# CL02.net
KiCad netlist of a schematic drawn in EAGLE
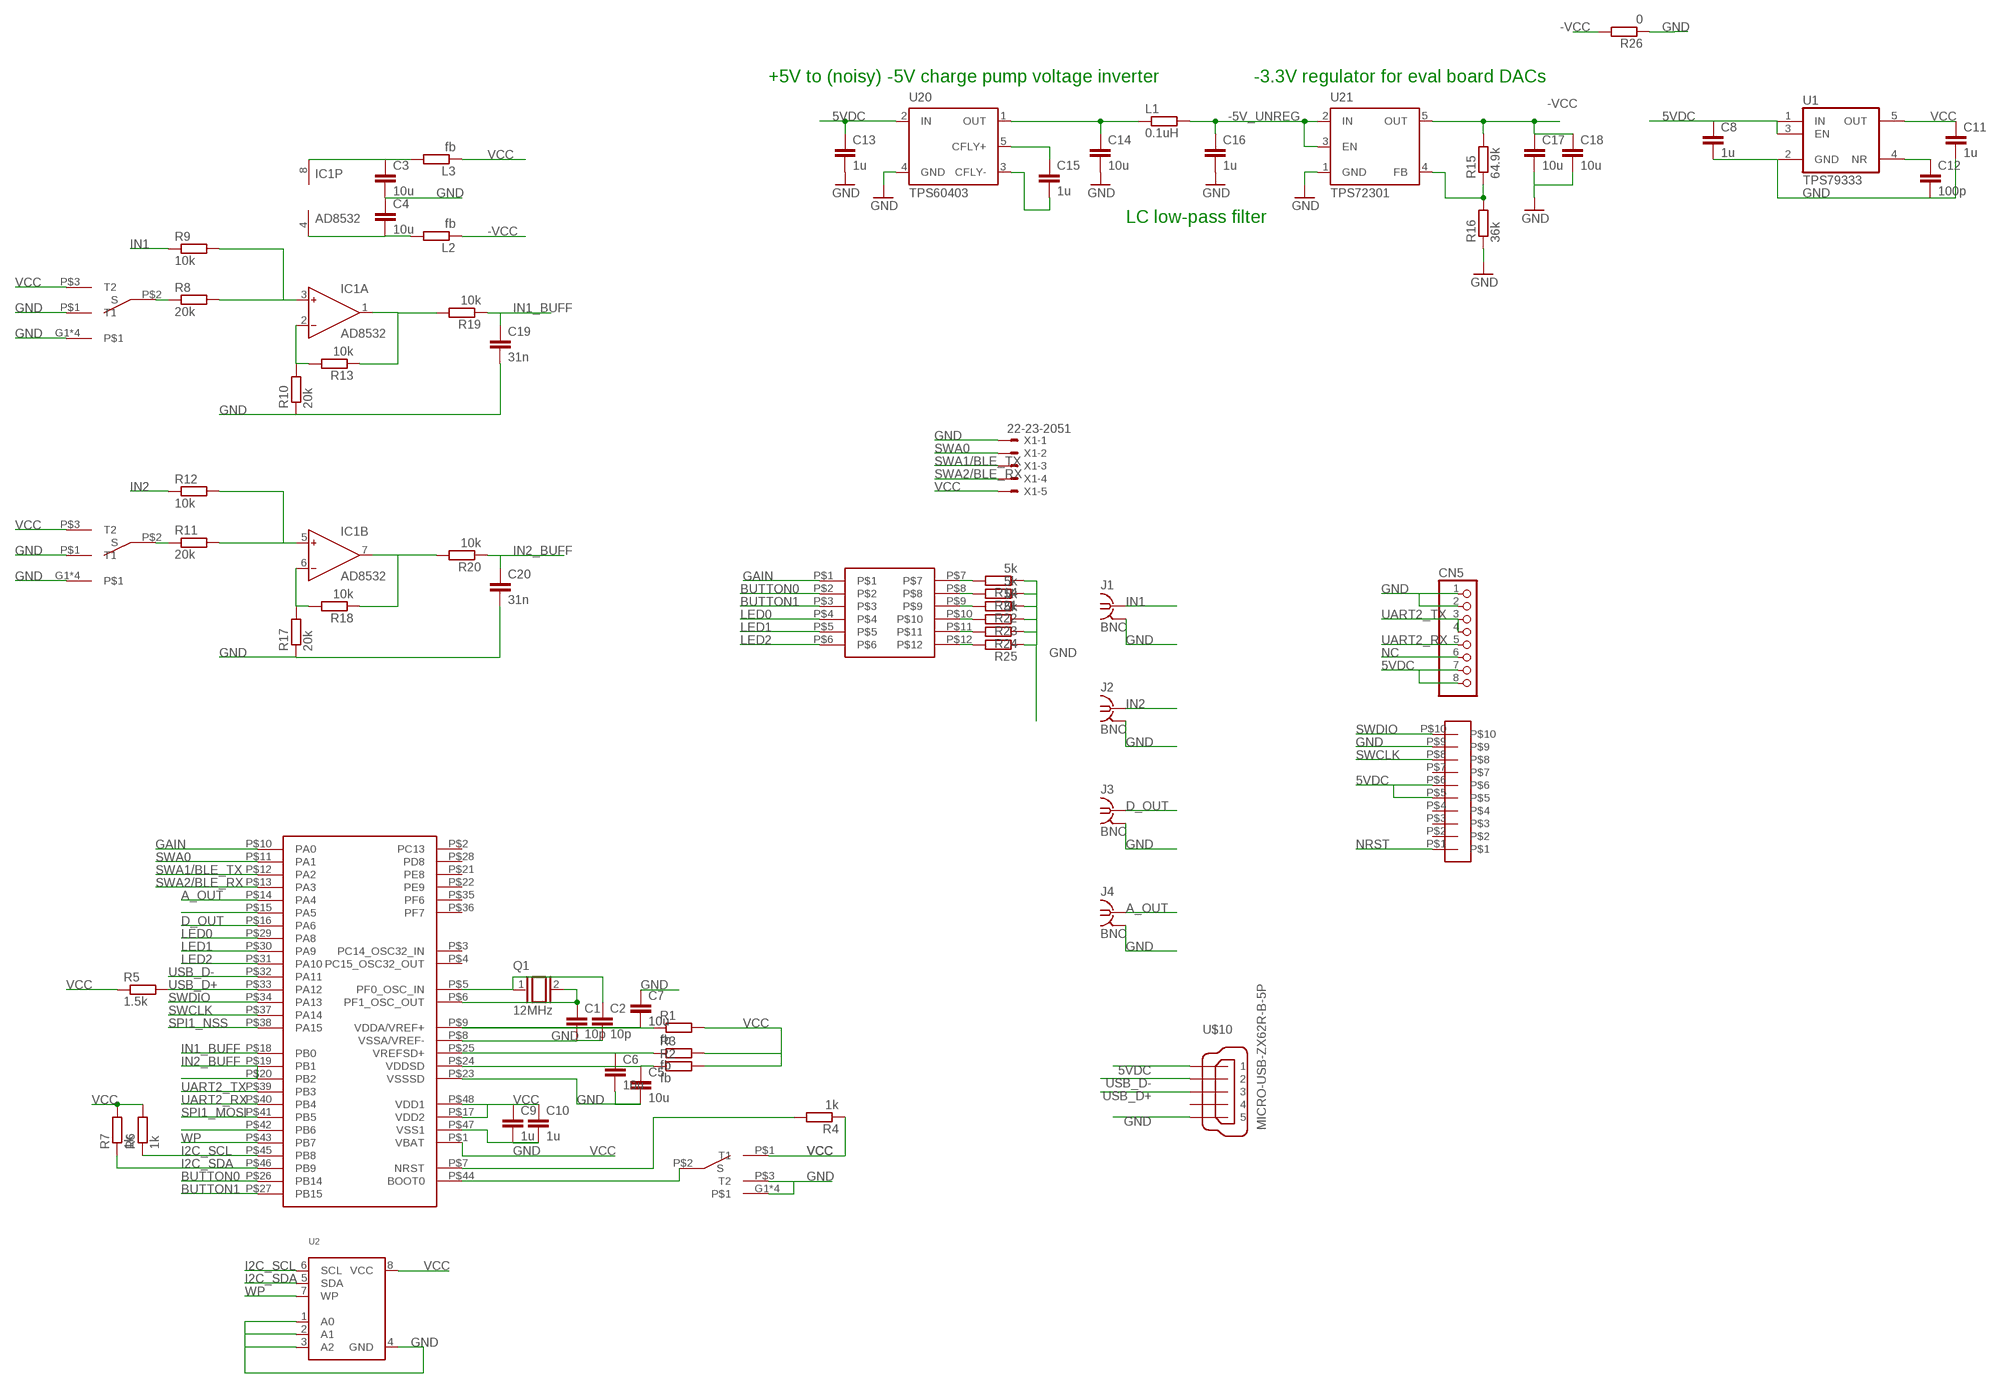
[diagram p0: schematic, sheet 1]

(export (version "E")
  (design (tool "Eeschema 10.0.6"))
  (components
    (comp (ref "C1")
      (value "10p")
      (footprint "eagle-import:C0402")
      (libsource (lib "eagle-import") (part "CC0402"))
    )
    (comp (ref "C2")
      (value "10p")
      (footprint "eagle-import:C0402")
      (libsource (lib "eagle-import") (part "CC0402"))
    )
    (comp (ref "C3")
      (value "10u")
      (footprint "eagle-import:C0402")
      (libsource (lib "eagle-import") (part "CC0402"))
    )
    (comp (ref "C4")
      (value "10u")
      (footprint "eagle-import:C0402")
      (libsource (lib "eagle-import") (part "CC0402"))
    )
    (comp (ref "C5")
      (value "10u")
      (footprint "eagle-import:C0402")
      (libsource (lib "eagle-import") (part "CC0402"))
    )
    (comp (ref "C6")
      (value "10u")
      (footprint "eagle-import:C0402")
      (libsource (lib "eagle-import") (part "CC0402"))
    )
    (comp (ref "C7")
      (value "10u")
      (footprint "eagle-import:C0402")
      (libsource (lib "eagle-import") (part "CC0402"))
    )
    (comp (ref "C8")
      (value "1u")
      (footprint "eagle-import:C0402")
      (libsource (lib "eagle-import") (part "CC0402"))
    )
    (comp (ref "C9")
      (value "1u")
      (footprint "eagle-import:C0402")
      (libsource (lib "eagle-import") (part "CC0402"))
    )
    (comp (ref "C10")
      (value "1u")
      (footprint "eagle-import:C0402")
      (libsource (lib "eagle-import") (part "CC0402"))
    )
    (comp (ref "C11")
      (value "1u")
      (footprint "eagle-import:C0402")
      (libsource (lib "eagle-import") (part "CC0402"))
    )
    (comp (ref "C12")
      (value "100p")
      (footprint "eagle-import:C0402")
      (libsource (lib "eagle-import") (part "CC0402"))
    )
    (comp (ref "C13")
      (value "1u")
      (footprint "eagle-import:C0402")
      (libsource (lib "eagle-import") (part "CC0402"))
    )
    (comp (ref "C14")
      (value "10u")
      (footprint "eagle-import:C0402")
      (libsource (lib "eagle-import") (part "CC0402"))
    )
    (comp (ref "C15")
      (value "1u")
      (footprint "eagle-import:C0402")
      (libsource (lib "eagle-import") (part "CC0402"))
    )
    (comp (ref "C16")
      (value "1u")
      (footprint "eagle-import:C0402")
      (libsource (lib "eagle-import") (part "CC0402"))
    )
    (comp (ref "C17")
      (value "10u")
      (footprint "eagle-import:C0402")
      (libsource (lib "eagle-import") (part "CC0402"))
    )
    (comp (ref "C18")
      (value "10u")
      (footprint "eagle-import:C0402")
      (libsource (lib "eagle-import") (part "CC0402"))
    )
    (comp (ref "C19")
      (value "31n")
      (footprint "eagle-import:C0402")
      (libsource (lib "eagle-import") (part "CC0402"))
    )
    (comp (ref "C20")
      (value "31n")
      (footprint "eagle-import:C0402")
      (libsource (lib "eagle-import") (part "CC0402"))
    )
    (comp (ref "CN5")
      (value "JST_8PIN")
      (footprint "eagle-import:JSTPH8")
      (libsource (lib "eagle-import") (part "JST_8PIN"))
    )
    (comp (ref "IC1")
      (value "AD8532")
      (footprint "eagle-import:SO8")
      (fields (field (name "MF") "ALTERA CORPORATION") (field (name "MPN") "AD8542ARZ-REEL"))
      (libsource (lib "eagle-import") (part "AD8542R"))
    )
    (comp (ref "J1")
      (value "BNC")
      (footprint "eagle-import:BNC-SOCKET")
      (libsource (lib "eagle-import") (part "BNC"))
    )
    (comp (ref "J2")
      (value "BNC")
      (footprint "eagle-import:BNC-SOCKET")
      (libsource (lib "eagle-import") (part "BNC"))
    )
    (comp (ref "J3")
      (value "BNC")
      (footprint "eagle-import:BNC-SOCKET")
      (libsource (lib "eagle-import") (part "BNC"))
    )
    (comp (ref "J4")
      (value "BNC")
      (footprint "eagle-import:BNC-SOCKET")
      (libsource (lib "eagle-import") (part "BNC"))
    )
    (comp (ref "L1")
      (value "0.1uH")
      (footprint "eagle-import:R0402")
      (libsource (lib "eagle-import") (part "RR0402"))
    )
    (comp (ref "L2")
      (value "fb")
      (footprint "eagle-import:R0402")
      (libsource (lib "eagle-import") (part "RR0402"))
    )
    (comp (ref "L3")
      (value "fb")
      (footprint "eagle-import:R0402")
      (libsource (lib "eagle-import") (part "RR0402"))
    )
    (comp (ref "Q1")
      (value "12MHz")
      (footprint "eagle-import:QS")
      (libsource (lib "eagle-import") (part "XTAL/S"))
    )
    (comp (ref "R1")
      (value "fb")
      (footprint "eagle-import:R0402")
      (libsource (lib "eagle-import") (part "RR0402"))
    )
    (comp (ref "R2")
      (value "fb")
      (footprint "eagle-import:R0402")
      (libsource (lib "eagle-import") (part "RR0402"))
    )
    (comp (ref "R3")
      (value "fb")
      (footprint "eagle-import:R0402")
      (libsource (lib "eagle-import") (part "RR0402"))
    )
    (comp (ref "R4")
      (value "1k")
      (footprint "eagle-import:R0402")
      (libsource (lib "eagle-import") (part "RR0402"))
    )
    (comp (ref "R5")
      (value "1.5k")
      (footprint "eagle-import:R0402")
      (libsource (lib "eagle-import") (part "RR0402"))
    )
    (comp (ref "R6")
      (value "1k")
      (footprint "eagle-import:R0402")
      (libsource (lib "eagle-import") (part "RR0402"))
    )
    (comp (ref "R7")
      (value "1k")
      (footprint "eagle-import:R0402")
      (libsource (lib "eagle-import") (part "RR0402"))
    )
    (comp (ref "R8")
      (value "20k")
      (footprint "eagle-import:R0402")
      (libsource (lib "eagle-import") (part "RR0402"))
    )
    (comp (ref "R9")
      (value "10k")
      (footprint "eagle-import:R0402")
      (libsource (lib "eagle-import") (part "RR0402"))
    )
    (comp (ref "R10")
      (value "20k")
      (footprint "eagle-import:R0402")
      (libsource (lib "eagle-import") (part "RR0402"))
    )
    (comp (ref "R11")
      (value "20k")
      (footprint "eagle-import:R0402")
      (libsource (lib "eagle-import") (part "RR0402"))
    )
    (comp (ref "R12")
      (value "10k")
      (footprint "eagle-import:R0402")
      (libsource (lib "eagle-import") (part "RR0402"))
    )
    (comp (ref "R13")
      (value "10k")
      (footprint "eagle-import:R0402")
      (libsource (lib "eagle-import") (part "RR0402"))
    )
    (comp (ref "R14")
      (value "5k")
      (footprint "eagle-import:R0402")
      (libsource (lib "eagle-import") (part "RR0402"))
    )
    (comp (ref "R15")
      (value "64.9k")
      (footprint "eagle-import:R0402")
      (libsource (lib "eagle-import") (part "RR0402"))
    )
    (comp (ref "R16")
      (value "36k")
      (footprint "eagle-import:R0402")
      (libsource (lib "eagle-import") (part "RR0402"))
    )
    (comp (ref "R17")
      (value "20k")
      (footprint "eagle-import:R0402")
      (libsource (lib "eagle-import") (part "RR0402"))
    )
    (comp (ref "R18")
      (value "10k")
      (footprint "eagle-import:R0402")
      (libsource (lib "eagle-import") (part "RR0402"))
    )
    (comp (ref "R19")
      (value "10k")
      (footprint "eagle-import:R0402")
      (libsource (lib "eagle-import") (part "RR0402"))
    )
    (comp (ref "R20")
      (value "10k")
      (footprint "eagle-import:R0402")
      (libsource (lib "eagle-import") (part "RR0402"))
    )
    (comp (ref "R21")
      (value "5k")
      (footprint "eagle-import:R0402")
      (libsource (lib "eagle-import") (part "RR0402"))
    )
    (comp (ref "R22")
      (value "5k")
      (footprint "eagle-import:R0402")
      (libsource (lib "eagle-import") (part "RR0402"))
    )
    (comp (ref "R23")
      (value "5k")
      (footprint "eagle-import:R0402")
      (libsource (lib "eagle-import") (part "RR0402"))
    )
    (comp (ref "R24")
      (value "RR0402")
      (footprint "eagle-import:R0402")
      (libsource (lib "eagle-import") (part "RR0402"))
    )
    (comp (ref "R25")
      (value "RR0402")
      (footprint "eagle-import:R0402")
      (libsource (lib "eagle-import") (part "RR0402"))
    )
    (comp (ref "R26")
      (value "0")
      (footprint "eagle-import:R0402")
      (libsource (lib "eagle-import") (part "RR0402"))
    )
    (comp (ref "U$1")
      (value "STM32F373CCT6")
      (footprint "eagle-import:LQFP48")
      (libsource (lib "eagle-import") (part "STM32F373CCT6"))
    )
    (comp (ref "U$6")
      (value "CUS-12B")
      (footprint "eagle-import:CUS-12B")
      (libsource (lib "eagle-import") (part "CUS-12B"))
    )
    (comp (ref "U$7")
      (value "CUS-12B")
      (footprint "eagle-import:CUS-12B")
      (libsource (lib "eagle-import") (part "CUS-12B"))
    )
    (comp (ref "U$8")
      (value "2.54MM_2X6")
      (footprint "eagle-import:2.54MM_2X6")
      (libsource (lib "eagle-import") (part "2.54MM_2X6"))
    )
    (comp (ref "U$9")
      (value "2.54MM_2X5")
      (footprint "eagle-import:2.54MM_2X5")
      (libsource (lib "eagle-import") (part "2.54MM_2X5"))
    )
    (comp (ref "U$10")
      (value "MICRO-USB-ZX62R-B-5P")
      (footprint "eagle-import:ZX62R-B-5P")
      (libsource (lib "eagle-import") (part "MICRO-USB-ZX62R-B-5P"))
    )
    (comp (ref "U$12")
      (value "CUS-12B")
      (footprint "eagle-import:CUS-12B")
      (libsource (lib "eagle-import") (part "CUS-12B"))
    )
    (comp (ref "U1")
      (value "TPS79333")
      (footprint "eagle-import:TSOT-23-5")
      (libsource (lib "eagle-import") (part "TPS79333"))
    )
    (comp (ref "U2")
      (value "EEPROM_I2C_SOIC8_GENERIC")
      (footprint "eagle-import:SOIC8_150MIL")
      (libsource (lib "eagle-import") (part "EEPROM_I2C_SOIC8_GENERIC"))
    )
    (comp (ref "U20")
      (value "TPS60403")
      (footprint "eagle-import:SOT-23-5")
      (libsource (lib "eagle-import") (part "TPS60403"))
    )
    (comp (ref "U21")
      (value "TPS72301")
      (footprint "eagle-import:SOT-23-5")
      (libsource (lib "eagle-import") (part "TPS72301"))
    )
    (comp (ref "X1")
      (value "22-23-2051")
      (footprint "eagle-import:22-23-2051")
      (fields (field (name "MF") "MOLEX"))
      (libsource (lib "eagle-import") (part "22-23-2051"))
    )
  )
  (nets
    (net (code "1") (name "/-5V_UNREG") (class "Default")
      (node (ref "C16") (pin "1") (pinfunction "1_1") (pintype "passive"))
      (node (ref "L1") (pin "2") (pinfunction "2_2") (pintype "passive"))
      (node (ref "U21") (pin "2") (pinfunction "IN_2") (pintype "power_in"))
      (node (ref "U21") (pin "3") (pinfunction "EN_3") (pintype "input"))
    )
    (net (code "2") (name "/-VCC") (class "Default")
      (node (ref "C17") (pin "1") (pinfunction "1_1") (pintype "passive"))
      (node (ref "C18") (pin "1") (pinfunction "1_1") (pintype "passive"))
      (node (ref "L2") (pin "1") (pinfunction "1_1") (pintype "passive"))
      (node (ref "R15") (pin "2") (pinfunction "2_2") (pintype "passive"))
      (node (ref "R26") (pin "2") (pinfunction "2_2") (pintype "passive"))
      (node (ref "U21") (pin "5") (pinfunction "OUT_5") (pintype "power_in"))
    )
    (net (code "3") (name "/5VDC") (class "Default")
      (node (ref "C13") (pin "1") (pinfunction "1_1") (pintype "passive"))
      (node (ref "C8") (pin "1") (pinfunction "1_1") (pintype "passive"))
      (node (ref "CN5") (pin "7") (pinfunction "7_7") (pintype "passive"))
      (node (ref "CN5") (pin "8") (pinfunction "8_8") (pintype "passive"))
      (node (ref "U$10") (pin "1") (pinfunction "1_1") (pintype "input"))
      (node (ref "U$9") (pin "P$5") (pinfunction "P$5_P$5") (pintype "bidirectional"))
      (node (ref "U$9") (pin "P$6") (pinfunction "P$6_P$6") (pintype "bidirectional"))
      (node (ref "U1") (pin "1") (pinfunction "IN_1") (pintype "power_in"))
      (node (ref "U1") (pin "3") (pinfunction "EN_3") (pintype "input"))
      (node (ref "U20") (pin "2") (pinfunction "IN_2") (pintype "power_in"))
    )
    (net (code "4") (name "/A_OUT") (class "Default")
      (node (ref "J4") (pin "A") (pinfunction "1_A") (pintype "passive"))
      (node (ref "U$1") (pin "P$14") (pinfunction "PA4_P$14") (pintype "bidirectional"))
    )
    (net (code "5") (name "/BUTTON0") (class "Default")
      (node (ref "U$1") (pin "P$26") (pinfunction "PB14_P$26") (pintype "bidirectional"))
      (node (ref "U$8") (pin "P$2") (pinfunction "P$2_P$2") (pintype "bidirectional"))
    )
    (net (code "6") (name "/BUTTON1") (class "Default")
      (node (ref "U$1") (pin "P$27") (pinfunction "PB15_P$27") (pintype "bidirectional"))
      (node (ref "U$8") (pin "P$3") (pinfunction "P$3_P$3") (pintype "bidirectional"))
    )
    (net (code "7") (name "/D_OUT") (class "Default")
      (node (ref "J3") (pin "A") (pinfunction "1_A") (pintype "passive"))
      (node (ref "U$1") (pin "P$16") (pinfunction "PA6_P$16") (pintype "bidirectional"))
    )
    (net (code "8") (name "/GAIN") (class "Default")
      (node (ref "U$1") (pin "P$10") (pinfunction "PA0_P$10") (pintype "bidirectional"))
      (node (ref "U$8") (pin "P$1") (pinfunction "P$1_P$1") (pintype "bidirectional"))
    )
    (net (code "9") (name "/I2C_SCL") (class "Default")
      (node (ref "R6") (pin "1") (pinfunction "1_1") (pintype "passive"))
      (node (ref "U$1") (pin "P$45") (pinfunction "PB8_P$45") (pintype "bidirectional"))
      (node (ref "U2") (pin "6") (pinfunction "SCL_6") (pintype "input"))
    )
    (net (code "10") (name "/I2C_SDA") (class "Default")
      (node (ref "R7") (pin "1") (pinfunction "1_1") (pintype "passive"))
      (node (ref "U$1") (pin "P$46") (pinfunction "PB9_P$46") (pintype "bidirectional"))
      (node (ref "U2") (pin "5") (pinfunction "SDA_5") (pintype "bidirectional"))
    )
    (net (code "11") (name "/IN1") (class "Default")
      (node (ref "J1") (pin "A") (pinfunction "1_A") (pintype "passive"))
      (node (ref "R9") (pin "1") (pinfunction "1_1") (pintype "passive"))
    )
    (net (code "12") (name "/IN1_BUFF") (class "Default")
      (node (ref "C19") (pin "1") (pinfunction "1_1") (pintype "passive"))
      (node (ref "R19") (pin "1") (pinfunction "1_1") (pintype "passive"))
      (node (ref "U$1") (pin "P$18") (pinfunction "PB0_P$18") (pintype "bidirectional"))
    )
    (net (code "13") (name "/IN2") (class "Default")
      (node (ref "J2") (pin "A") (pinfunction "1_A") (pintype "passive"))
      (node (ref "R12") (pin "1") (pinfunction "1_1") (pintype "passive"))
    )
    (net (code "14") (name "/IN2_BUFF") (class "Default")
      (node (ref "C20") (pin "1") (pinfunction "1_1") (pintype "passive"))
      (node (ref "R20") (pin "1") (pinfunction "1_1") (pintype "passive"))
      (node (ref "U$1") (pin "P$19") (pinfunction "PB1_P$19") (pintype "bidirectional"))
      (node (ref "U$1") (pin "P$20") (pinfunction "PB2_P$20") (pintype "bidirectional"))
    )
    (net (code "15") (name "/LED0") (class "Default")
      (node (ref "U$1") (pin "P$29") (pinfunction "PA8_P$29") (pintype "bidirectional"))
      (node (ref "U$8") (pin "P$4") (pinfunction "P$4_P$4") (pintype "bidirectional"))
    )
    (net (code "16") (name "/LED1") (class "Default")
      (node (ref "U$1") (pin "P$30") (pinfunction "PA9_P$30") (pintype "bidirectional"))
      (node (ref "U$8") (pin "P$5") (pinfunction "P$5_P$5") (pintype "bidirectional"))
    )
    (net (code "17") (name "/LED2") (class "Default")
      (node (ref "U$1") (pin "P$31") (pinfunction "PA10_P$31") (pintype "bidirectional"))
      (node (ref "U$8") (pin "P$6") (pinfunction "P$6_P$6") (pintype "bidirectional"))
    )
    (net (code "18") (name "/NC") (class "Default")
      (node (ref "CN5") (pin "6") (pinfunction "6_6") (pintype "passive"))
    )
    (net (code "19") (name "/NRST") (class "Default")
      (node (ref "R4") (pin "2") (pinfunction "2_2") (pintype "passive"))
      (node (ref "U$1") (pin "P$7") (pinfunction "NRST_P$7") (pintype "bidirectional"))
      (node (ref "U$9") (pin "P$1") (pinfunction "P$1_P$1") (pintype "bidirectional"))
    )
    (net (code "20") (name "/SPI1_MOSI") (class "Default")
      (node (ref "U$1") (pin "P$41") (pinfunction "PB5_P$41") (pintype "bidirectional"))
    )
    (net (code "21") (name "/SPI1_NSS") (class "Default")
      (node (ref "U$1") (pin "P$38") (pinfunction "PA15_P$38") (pintype "bidirectional"))
    )
    (net (code "22") (name "/SWA0") (class "Default")
      (node (ref "U$1") (pin "P$11") (pinfunction "PA1_P$11") (pintype "bidirectional"))
      (node (ref "X1") (pin "2") (pinfunction "S_2") (pintype "passive"))
    )
    (net (code "23") (name "/SWA1{slash}BLE_TX") (class "Default")
      (node (ref "U$1") (pin "P$12") (pinfunction "PA2_P$12") (pintype "bidirectional"))
      (node (ref "X1") (pin "3") (pinfunction "S_3") (pintype "passive"))
    )
    (net (code "24") (name "/SWA2{slash}BLE_RX") (class "Default")
      (node (ref "U$1") (pin "P$13") (pinfunction "PA3_P$13") (pintype "bidirectional"))
      (node (ref "X1") (pin "4") (pinfunction "S_4") (pintype "passive"))
    )
    (net (code "25") (name "/SWCLK") (class "Default")
      (node (ref "U$1") (pin "P$37") (pinfunction "PA14_P$37") (pintype "bidirectional"))
      (node (ref "U$9") (pin "P$8") (pinfunction "P$8_P$8") (pintype "bidirectional"))
    )
    (net (code "26") (name "/SWDIO") (class "Default")
      (node (ref "U$1") (pin "P$34") (pinfunction "PA13_P$34") (pintype "bidirectional"))
      (node (ref "U$9") (pin "P$10") (pinfunction "P$10_P$10") (pintype "bidirectional"))
    )
    (net (code "27") (name "/UART2_RX") (class "Default")
      (node (ref "CN5") (pin "5") (pinfunction "5_5") (pintype "passive"))
      (node (ref "U$1") (pin "P$40") (pinfunction "PB4_P$40") (pintype "bidirectional"))
    )
    (net (code "28") (name "/UART2_TX") (class "Default")
      (node (ref "CN5") (pin "3") (pinfunction "3_3") (pintype "passive"))
      (node (ref "CN5") (pin "4") (pinfunction "4_4") (pintype "passive"))
      (node (ref "U$1") (pin "P$39") (pinfunction "PB3_P$39") (pintype "bidirectional"))
    )
    (net (code "29") (name "/USB_D+") (class "Default")
      (node (ref "R5") (pin "2") (pinfunction "2_2") (pintype "passive"))
      (node (ref "U$1") (pin "P$33") (pinfunction "PA12_P$33") (pintype "bidirectional"))
      (node (ref "U$10") (pin "3") (pinfunction "3_3") (pintype "input"))
    )
    (net (code "30") (name "/USB_D-") (class "Default")
      (node (ref "U$1") (pin "P$32") (pinfunction "PA11_P$32") (pintype "bidirectional"))
      (node (ref "U$10") (pin "2") (pinfunction "2_2") (pintype "input"))
    )
    (net (code "31") (name "/VCC") (class "Default")
      (node (ref "C10") (pin "1") (pinfunction "1_1") (pintype "passive"))
      (node (ref "C11") (pin "1") (pinfunction "1_1") (pintype "passive"))
      (node (ref "C9") (pin "1") (pinfunction "1_1") (pintype "passive"))
      (node (ref "L3") (pin "1") (pinfunction "1_1") (pintype "passive"))
      (node (ref "R1") (pin "2") (pinfunction "2_2") (pintype "passive"))
      (node (ref "R2") (pin "2") (pinfunction "2_2") (pintype "passive"))
      (node (ref "R3") (pin "2") (pinfunction "2_2") (pintype "passive"))
      (node (ref "R4") (pin "1") (pinfunction "1_1") (pintype "passive"))
      (node (ref "R5") (pin "1") (pinfunction "1_1") (pintype "passive"))
      (node (ref "R6") (pin "2") (pinfunction "2_2") (pintype "passive"))
      (node (ref "R7") (pin "2") (pinfunction "2_2") (pintype "passive"))
      (node (ref "U$1") (pin "P$1") (pinfunction "VBAT_P$1") (pintype "bidirectional"))
      (node (ref "U$1") (pin "P$17") (pinfunction "VDD2_P$17") (pintype "bidirectional"))
      (node (ref "U$1") (pin "P$48") (pinfunction "VDD1_P$48") (pintype "bidirectional"))
      (node (ref "U$12") (pin "P$1") (pinfunction "T1_P$1") (pintype "bidirectional"))
      (node (ref "U$6") (pin "P$3") (pinfunction "T2_P$3") (pintype "bidirectional"))
      (node (ref "U$7") (pin "P$3") (pinfunction "T2_P$3") (pintype "bidirectional"))
      (node (ref "U1") (pin "5") (pinfunction "OUT_5") (pintype "power_in"))
      (node (ref "U2") (pin "8") (pinfunction "VCC_8") (pintype "power_in"))
      (node (ref "X1") (pin "5") (pinfunction "S_5") (pintype "passive"))
    )
    (net (code "32") (name "/WP") (class "Default")
      (node (ref "U$1") (pin "P$43") (pinfunction "PB7_P$43") (pintype "bidirectional"))
      (node (ref "U2") (pin "7") (pinfunction "WP_7") (pintype "input"))
    )
    (net (code "33") (name "GND") (class "Default")
      (node (ref "C1") (pin "2") (pinfunction "2_2") (pintype "passive"))
      (node (ref "C10") (pin "2") (pinfunction "2_2") (pintype "passive"))
      (node (ref "C11") (pin "2") (pinfunction "2_2") (pintype "passive"))
      (node (ref "C12") (pin "2") (pinfunction "2_2") (pintype "passive"))
      (node (ref "C13") (pin "2") (pinfunction "2_2") (pintype "passive"))
      (node (ref "C14") (pin "2") (pinfunction "2_2") (pintype "passive"))
      (node (ref "C16") (pin "2") (pinfunction "2_2") (pintype "passive"))
      (node (ref "C17") (pin "2") (pinfunction "2_2") (pintype "passive"))
      (node (ref "C18") (pin "2") (pinfunction "2_2") (pintype "passive"))
      (node (ref "C19") (pin "2") (pinfunction "2_2") (pintype "passive"))
      (node (ref "C2") (pin "2") (pinfunction "2_2") (pintype "passive"))
      (node (ref "C20") (pin "2") (pinfunction "2_2") (pintype "passive"))
      (node (ref "C3") (pin "2") (pinfunction "2_2") (pintype "passive"))
      (node (ref "C4") (pin "1") (pinfunction "1_1") (pintype "passive"))
      (node (ref "C5") (pin "2") (pinfunction "2_2") (pintype "passive"))
      (node (ref "C6") (pin "2") (pinfunction "2_2") (pintype "passive"))
      (node (ref "C7") (pin "1") (pinfunction "1_1") (pintype "passive"))
      (node (ref "C8") (pin "2") (pinfunction "2_2") (pintype "passive"))
      (node (ref "C9") (pin "2") (pinfunction "2_2") (pintype "passive"))
      (node (ref "CN5") (pin "1") (pinfunction "1_1") (pintype "passive"))
      (node (ref "CN5") (pin "2") (pinfunction "2_2") (pintype "passive"))
      (node (ref "J1") (pin "SH") (pinfunction "SH_SH") (pintype "power_in"))
      (node (ref "J2") (pin "SH") (pinfunction "SH_SH") (pintype "power_in"))
      (node (ref "J3") (pin "SH") (pinfunction "SH_SH") (pintype "power_in"))
      (node (ref "J4") (pin "SH") (pinfunction "SH_SH") (pintype "power_in"))
      (node (ref "R10") (pin "1") (pinfunction "1_1") (pintype "passive"))
      (node (ref "R14") (pin "1") (pinfunction "1_1") (pintype "passive"))
      (node (ref "R16") (pin "1") (pinfunction "1_1") (pintype "passive"))
      (node (ref "R17") (pin "1") (pinfunction "1_1") (pintype "passive"))
      (node (ref "R21") (pin "1") (pinfunction "1_1") (pintype "passive"))
      (node (ref "R22") (pin "1") (pinfunction "1_1") (pintype "passive"))
      (node (ref "R23") (pin "1") (pinfunction "1_1") (pintype "passive"))
      (node (ref "R24") (pin "1") (pinfunction "1_1") (pintype "passive"))
      (node (ref "R25") (pin "1") (pinfunction "1_1") (pintype "passive"))
      (node (ref "R26") (pin "1") (pinfunction "1_1") (pintype "passive"))
      (node (ref "U$1") (pin "P$23") (pinfunction "VSSSD_P$23") (pintype "bidirectional"))
      (node (ref "U$1") (pin "P$47") (pinfunction "VSS1_P$47") (pintype "bidirectional"))
      (node (ref "U$1") (pin "P$8") (pinfunction "VSSA/VREF-_P$8") (pintype "bidirectional"))
      (node (ref "U$10") (pin "5") (pinfunction "5_5") (pintype "input"))
      (node (ref "U$12") (pin "G1") (pinfunction "P$1_G1") (pintype "bidirectional"))
      (node (ref "U$12") (pin "G2") (pinfunction "P$1_G2") (pintype "bidirectional"))
      (node (ref "U$12") (pin "G3") (pinfunction "P$1_G3") (pintype "bidirectional"))
      (node (ref "U$12") (pin "G4") (pinfunction "P$1_G4") (pintype "bidirectional"))
      (node (ref "U$12") (pin "P$3") (pinfunction "T2_P$3") (pintype "bidirectional"))
      (node (ref "U$6") (pin "G1") (pinfunction "P$1_G1") (pintype "bidirectional"))
      (node (ref "U$6") (pin "G2") (pinfunction "P$1_G2") (pintype "bidirectional"))
      (node (ref "U$6") (pin "G3") (pinfunction "P$1_G3") (pintype "bidirectional"))
      (node (ref "U$6") (pin "G4") (pinfunction "P$1_G4") (pintype "bidirectional"))
      (node (ref "U$6") (pin "P$1") (pinfunction "T1_P$1") (pintype "bidirectional"))
      (node (ref "U$7") (pin "G1") (pinfunction "P$1_G1") (pintype "bidirectional"))
      (node (ref "U$7") (pin "G2") (pinfunction "P$1_G2") (pintype "bidirectional"))
      (node (ref "U$7") (pin "G3") (pinfunction "P$1_G3") (pintype "bidirectional"))
      (node (ref "U$7") (pin "G4") (pinfunction "P$1_G4") (pintype "bidirectional"))
      (node (ref "U$7") (pin "P$1") (pinfunction "T1_P$1") (pintype "bidirectional"))
      (node (ref "U$9") (pin "P$9") (pinfunction "P$9_P$9") (pintype "bidirectional"))
      (node (ref "U1") (pin "2") (pinfunction "GND_2") (pintype "power_in"))
      (node (ref "U2") (pin "1") (pinfunction "A0_1") (pintype "input"))
      (node (ref "U2") (pin "2") (pinfunction "A1_2") (pintype "input"))
      (node (ref "U2") (pin "3") (pinfunction "A2_3") (pintype "input"))
      (node (ref "U2") (pin "4") (pinfunction "GND_4") (pintype "power_in"))
      (node (ref "U20") (pin "4") (pinfunction "GND_4") (pintype "power_in"))
      (node (ref "U21") (pin "1") (pinfunction "GND_1") (pintype "power_in"))
      (node (ref "X1") (pin "1") (pinfunction "S_1") (pintype "passive"))
    )
    (net (code "34") (name "Net-(IC1A-IN+)") (class "Default")
      (node (ref "IC1") (pin "3") (pinfunction "IN+_3") (pintype "input"))
      (node (ref "R8") (pin "2") (pinfunction "2_2") (pintype "passive"))
      (node (ref "R9") (pin "2") (pinfunction "2_2") (pintype "passive"))
    )
    (net (code "35") (name "Net-(IC1A-IN-)") (class "Default")
      (node (ref "IC1") (pin "2") (pinfunction "IN-_2") (pintype "input"))
      (node (ref "R10") (pin "2") (pinfunction "2_2") (pintype "passive"))
      (node (ref "R13") (pin "2") (pinfunction "2_2") (pintype "passive"))
    )
    (net (code "36") (name "Net-(IC1A-OUT)") (class "Default")
      (node (ref "IC1") (pin "1") (pinfunction "OUT_1") (pintype "output"))
      (node (ref "R13") (pin "1") (pinfunction "1_1") (pintype "passive"))
      (node (ref "R19") (pin "2") (pinfunction "2_2") (pintype "passive"))
    )
    (net (code "37") (name "Net-(IC1B-IN+)") (class "Default")
      (node (ref "IC1") (pin "5") (pinfunction "IN+_5") (pintype "input"))
      (node (ref "R11") (pin "2") (pinfunction "2_2") (pintype "passive"))
      (node (ref "R12") (pin "2") (pinfunction "2_2") (pintype "passive"))
    )
    (net (code "38") (name "Net-(IC1B-IN-)") (class "Default")
      (node (ref "IC1") (pin "6") (pinfunction "IN-_6") (pintype "input"))
      (node (ref "R17") (pin "2") (pinfunction "2_2") (pintype "passive"))
      (node (ref "R18") (pin "2") (pinfunction "2_2") (pintype "passive"))
    )
    (net (code "39") (name "Net-(IC1B-OUT)") (class "Default")
      (node (ref "IC1") (pin "7") (pinfunction "OUT_7") (pintype "output"))
      (node (ref "R18") (pin "1") (pinfunction "1_1") (pintype "passive"))
      (node (ref "R20") (pin "2") (pinfunction "2_2") (pintype "passive"))
    )
    (net (code "40") (name "Net-(IC1C-V+)") (class "Default")
      (node (ref "C3") (pin "1") (pinfunction "1_1") (pintype "passive"))
      (node (ref "IC1") (pin "8") (pinfunction "V+_8") (pintype "power_in"))
      (node (ref "L3") (pin "2") (pinfunction "2_2") (pintype "passive"))
    )
    (net (code "41") (name "Net-(IC1C-V-)") (class "Default")
      (node (ref "C4") (pin "2") (pinfunction "2_2") (pintype "passive"))
      (node (ref "IC1") (pin "4") (pinfunction "V-_4") (pintype "power_in"))
      (node (ref "L2") (pin "2") (pinfunction "2_2") (pintype "passive"))
    )
    (net (code "42") (name "Net-(R14-Pad2)") (class "Default")
      (node (ref "R14") (pin "2") (pinfunction "2_2") (pintype "passive"))
      (node (ref "U$8") (pin "P$7") (pinfunction "P$7_P$7") (pintype "bidirectional"))
    )
    (net (code "43") (name "Net-(R21-Pad2)") (class "Default")
      (node (ref "R21") (pin "2") (pinfunction "2_2") (pintype "passive"))
      (node (ref "U$8") (pin "P$8") (pinfunction "P$8_P$8") (pintype "bidirectional"))
    )
    (net (code "44") (name "Net-(R22-Pad2)") (class "Default")
      (node (ref "R22") (pin "2") (pinfunction "2_2") (pintype "passive"))
      (node (ref "U$8") (pin "P$9") (pinfunction "P$9_P$9") (pintype "bidirectional"))
    )
    (net (code "45") (name "Net-(R23-Pad2)") (class "Default")
      (node (ref "R23") (pin "2") (pinfunction "2_2") (pintype "passive"))
      (node (ref "U$8") (pin "P$10") (pinfunction "P$10_P$10") (pintype "bidirectional"))
    )
    (net (code "46") (name "Net-(R24-Pad2)") (class "Default")
      (node (ref "R24") (pin "2") (pinfunction "2_2") (pintype "passive"))
      (node (ref "U$8") (pin "P$11") (pinfunction "P$11_P$11") (pintype "bidirectional"))
    )
    (net (code "47") (name "Net-(R25-Pad2)") (class "Default")
      (node (ref "R25") (pin "2") (pinfunction "2_2") (pintype "passive"))
      (node (ref "U$8") (pin "P$12") (pinfunction "P$12_P$12") (pintype "bidirectional"))
    )
    (net (code "48") (name "Net-(U$1-BOOT0)") (class "Default")
      (node (ref "U$1") (pin "P$44") (pinfunction "BOOT0_P$44") (pintype "bidirectional"))
      (node (ref "U$12") (pin "P$2") (pinfunction "S_P$2") (pintype "bidirectional"))
    )
    (net (code "49") (name "Net-(U$1-PF0_OSC_IN)") (class "Default")
      (node (ref "C2") (pin "1") (pinfunction "1_1") (pintype "passive"))
      (node (ref "Q1") (pin "1") (pinfunction "1_1") (pintype "passive"))
      (node (ref "U$1") (pin "P$5") (pinfunction "PF0_OSC_IN_P$5") (pintype "bidirectional"))
    )
    (net (code "50") (name "Net-(U$1-PF1_OSC_OUT)") (class "Default")
      (node (ref "C1") (pin "1") (pinfunction "1_1") (pintype "passive"))
      (node (ref "Q1") (pin "2") (pinfunction "2_2") (pintype "passive"))
      (node (ref "U$1") (pin "P$6") (pinfunction "PF1_OSC_OUT_P$6") (pintype "bidirectional"))
    )
    (net (code "51") (name "Net-(U$1-VDDA{slash}VREF+)") (class "Default")
      (node (ref "C7") (pin "2") (pinfunction "2_2") (pintype "passive"))
      (node (ref "R1") (pin "1") (pinfunction "1_1") (pintype "passive"))
      (node (ref "U$1") (pin "P$9") (pinfunction "VDDA/VREF+_P$9") (pintype "bidirectional"))
    )
    (net (code "52") (name "Net-(U$1-VDDSD)") (class "Default")
      (node (ref "C5") (pin "1") (pinfunction "1_1") (pintype "passive"))
      (node (ref "R2") (pin "1") (pinfunction "1_1") (pintype "passive"))
      (node (ref "U$1") (pin "P$24") (pinfunction "VDDSD_P$24") (pintype "bidirectional"))
    )
    (net (code "53") (name "Net-(U$1-VREFSD+)") (class "Default")
      (node (ref "C6") (pin "1") (pinfunction "1_1") (pintype "passive"))
      (node (ref "R3") (pin "1") (pinfunction "1_1") (pintype "passive"))
      (node (ref "U$1") (pin "P$25") (pinfunction "VREFSD+_P$25") (pintype "bidirectional"))
    )
    (net (code "54") (name "Net-(U$6A-S)") (class "Default")
      (node (ref "R8") (pin "1") (pinfunction "1_1") (pintype "passive"))
      (node (ref "U$6") (pin "P$2") (pinfunction "S_P$2") (pintype "bidirectional"))
    )
    (net (code "55") (name "Net-(U$7A-S)") (class "Default")
      (node (ref "R11") (pin "1") (pinfunction "1_1") (pintype "passive"))
      (node (ref "U$7") (pin "P$2") (pinfunction "S_P$2") (pintype "bidirectional"))
    )
    (net (code "56") (name "Net-(U1-NR)") (class "Default")
      (node (ref "C12") (pin "1") (pinfunction "1_1") (pintype "passive"))
      (node (ref "U1") (pin "4") (pinfunction "NR_4") (pintype "passive"))
    )
    (net (code "57") (name "Net-(U20-CFLY+)") (class "Default")
      (node (ref "C15") (pin "1") (pinfunction "1_1") (pintype "passive"))
      (node (ref "U20") (pin "5") (pinfunction "CFLY+_5") (pintype "passive"))
    )
    (net (code "58") (name "Net-(U20-CFLY-)") (class "Default")
      (node (ref "C15") (pin "2") (pinfunction "2_2") (pintype "passive"))
      (node (ref "U20") (pin "3") (pinfunction "CFLY-_3") (pintype "passive"))
    )
    (net (code "59") (name "Net-(U20-OUT)") (class "Default")
      (node (ref "C14") (pin "1") (pinfunction "1_1") (pintype "passive"))
      (node (ref "L1") (pin "1") (pinfunction "1_1") (pintype "passive"))
      (node (ref "U20") (pin "1") (pinfunction "OUT_1") (pintype "power_in"))
    )
    (net (code "60") (name "Net-(U21-FB)") (class "Default")
      (node (ref "R15") (pin "1") (pinfunction "1_1") (pintype "passive"))
      (node (ref "R16") (pin "2") (pinfunction "2_2") (pintype "passive"))
      (node (ref "U21") (pin "4") (pinfunction "FB_4") (pintype "input"))
    )
    (net (code "61") (name "unconnected-(U$1-PA5-PadP$15)") (class "Default")
      (node (ref "U$1") (pin "P$15") (pinfunction "PA5_P$15") (pintype "bidirectional"))
    )
    (net (code "62") (name "unconnected-(U$1-PB6-PadP$42)") (class "Default")
      (node (ref "U$1") (pin "P$42") (pinfunction "PB6_P$42") (pintype "bidirectional"))
    )
    (net (code "63") (name "unconnected-(U$1-PC13-PadP$2)") (class "Default")
      (node (ref "U$1") (pin "P$2") (pinfunction "PC13_P$2") (pintype "bidirectional"))
    )
    (net (code "64") (name "unconnected-(U$1-PC14_OSC32_IN-PadP$3)") (class "Default")
      (node (ref "U$1") (pin "P$3") (pinfunction "PC14_OSC32_IN_P$3") (pintype "bidirectional"))
    )
    (net (code "65") (name "unconnected-(U$1-PC15_OSC32_OUT-PadP$4)") (class "Default")
      (node (ref "U$1") (pin "P$4") (pinfunction "PC15_OSC32_OUT_P$4") (pintype "bidirectional"))
    )
    (net (code "66") (name "unconnected-(U$1-PD8-PadP$28)") (class "Default")
      (node (ref "U$1") (pin "P$28") (pinfunction "PD8_P$28") (pintype "bidirectional"))
    )
    (net (code "67") (name "unconnected-(U$1-PE8-PadP$21)") (class "Default")
      (node (ref "U$1") (pin "P$21") (pinfunction "PE8_P$21") (pintype "bidirectional"))
    )
    (net (code "68") (name "unconnected-(U$1-PE9-PadP$22)") (class "Default")
      (node (ref "U$1") (pin "P$22") (pinfunction "PE9_P$22") (pintype "bidirectional"))
    )
    (net (code "69") (name "unconnected-(U$1-PF6-PadP$35)") (class "Default")
      (node (ref "U$1") (pin "P$35") (pinfunction "PF6_P$35") (pintype "bidirectional"))
    )
    (net (code "70") (name "unconnected-(U$1-PF7-PadP$36)") (class "Default")
      (node (ref "U$1") (pin "P$36") (pinfunction "PF7_P$36") (pintype "bidirectional"))
    )
    (net (code "71") (name "unconnected-(U$9-PadP$2)") (class "Default")
      (node (ref "U$9") (pin "P$2") (pinfunction "P$2_P$2") (pintype "bidirectional"))
    )
    (net (code "72") (name "unconnected-(U$9-PadP$3)") (class "Default")
      (node (ref "U$9") (pin "P$3") (pinfunction "P$3_P$3") (pintype "bidirectional"))
    )
    (net (code "73") (name "unconnected-(U$9-PadP$4)") (class "Default")
      (node (ref "U$9") (pin "P$4") (pinfunction "P$4_P$4") (pintype "bidirectional"))
    )
    (net (code "74") (name "unconnected-(U$9-PadP$7)") (class "Default")
      (node (ref "U$9") (pin "P$7") (pinfunction "P$7_P$7") (pintype "bidirectional"))
    )
    (net (code "75") (name "unconnected-(U$10-Pad4)") (class "Default")
      (node (ref "U$10") (pin "4") (pinfunction "4_4") (pintype "input"))
    )
  )
)
